# preamp.net
KiCad netlist of a schematic drawn in EAGLE
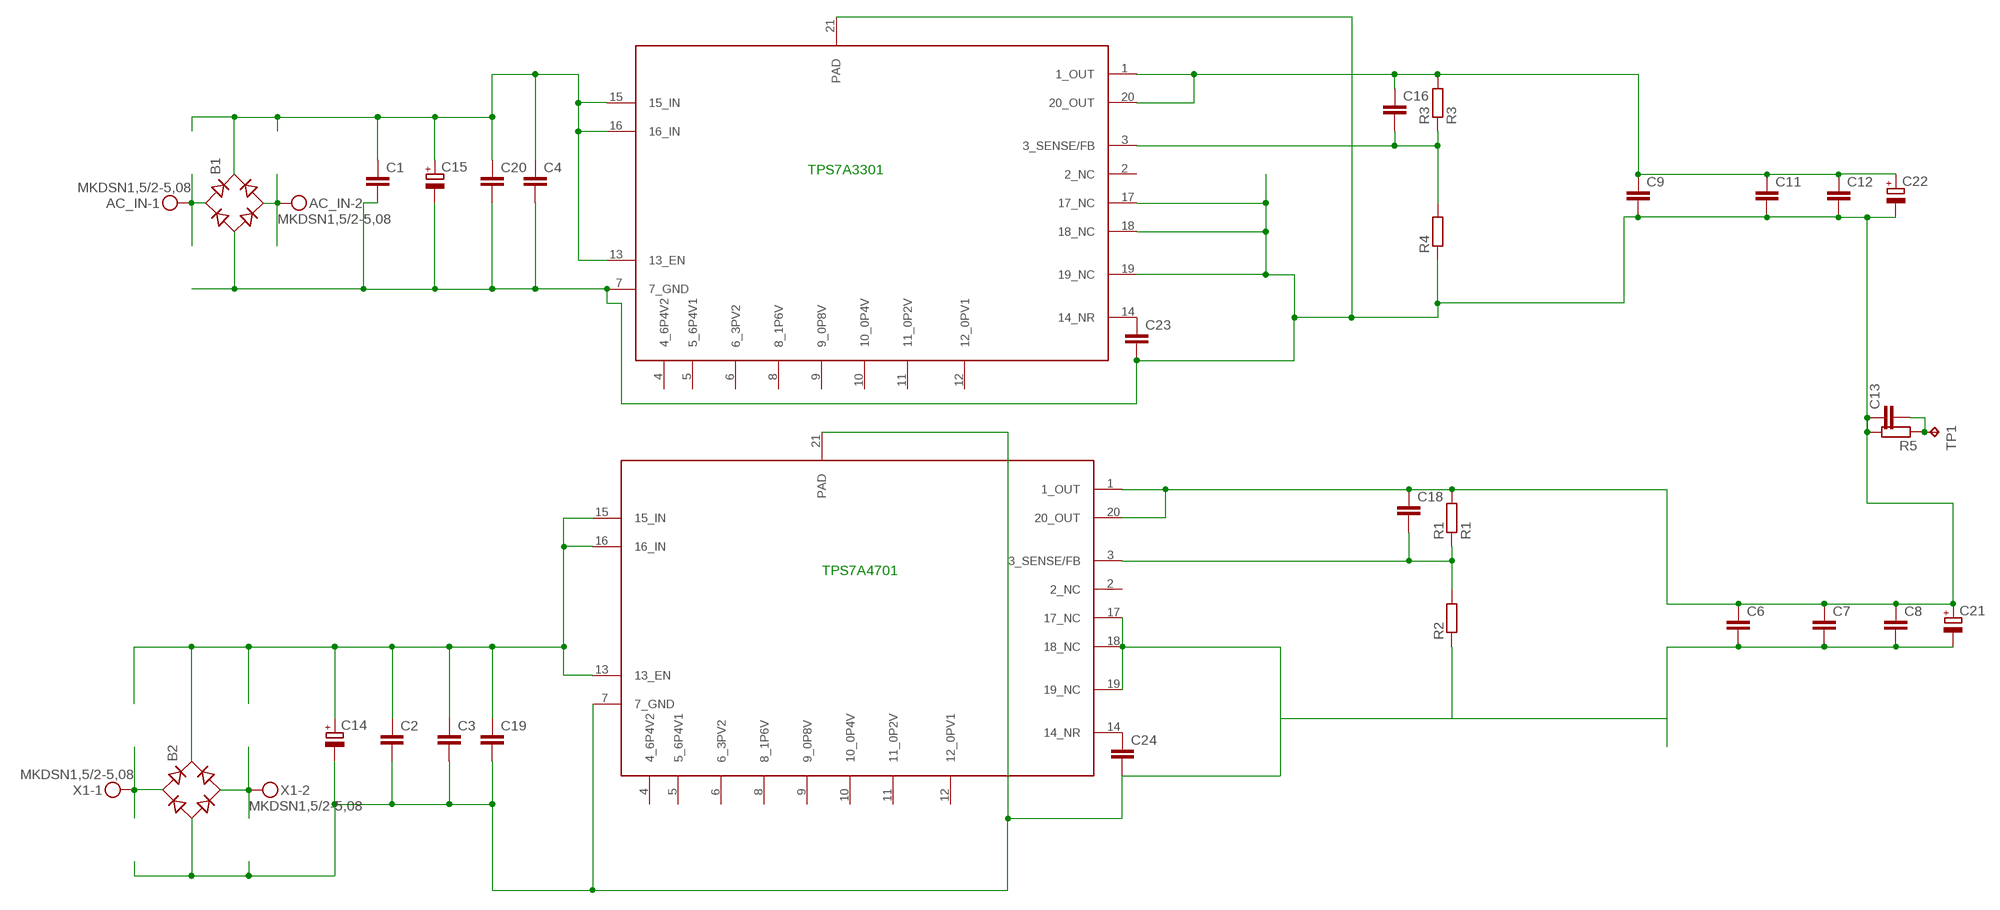
[diagram p0: schematic, sheet 1]
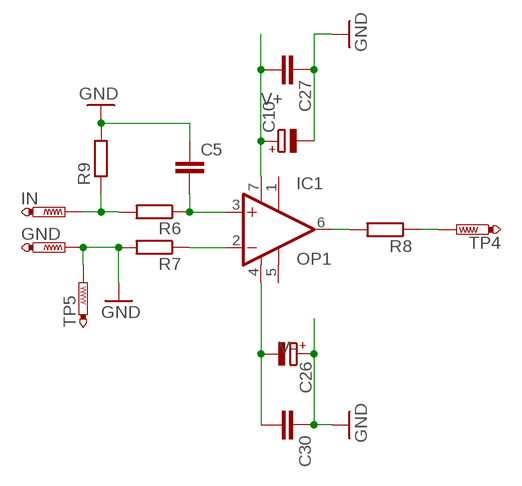
[diagram p1: schematic, sheet 2]

(export (version "E")
  (design (tool "Eeschema 10.0.6"))
  (components
    (comp (ref "AC_IN")
      (value "MKDSN1,5/2-5,08")
      (footprint "eagle-import:MKDSN1,5_2-5,08")
      (libsource (lib "eagle-import") (part "MKDSN1,5/2-5,08"))
    )
    (comp (ref "B1")
      (value "RB1A")
      (footprint "eagle-import:RB1A")
      (libsource (lib "eagle-import") (part "RB1A"))
    )
    (comp (ref "B2")
      (value "RB1A")
      (footprint "eagle-import:RB1A")
      (libsource (lib "eagle-import") (part "RB1A"))
    )
    (comp (ref "C1")
      (value "C-EUC1210")
      (footprint "eagle-import:C1210")
      (libsource (lib "eagle-import") (part "C-EUC1210"))
    )
    (comp (ref "C2")
      (value "C-EUC1210")
      (footprint "eagle-import:C1210")
      (libsource (lib "eagle-import") (part "C-EUC1210"))
    )
    (comp (ref "C3")
      (value "C-EUC0805")
      (footprint "eagle-import:C0805")
      (libsource (lib "eagle-import") (part "C-EUC0805"))
    )
    (comp (ref "C4")
      (value "C-EUC0805")
      (footprint "eagle-import:C0805")
      (libsource (lib "eagle-import") (part "C-EUC0805"))
    )
    (comp (ref "C6")
      (value "C-EUC0603")
      (footprint "eagle-import:C0603")
      (libsource (lib "eagle-import") (part "C-EUC0603"))
    )
    (comp (ref "C7")
      (value "C-EUC0805")
      (footprint "eagle-import:C0805")
      (libsource (lib "eagle-import") (part "C-EUC0805"))
    )
    (comp (ref "C8")
      (value "C-EUC1210")
      (footprint "eagle-import:C1210")
      (libsource (lib "eagle-import") (part "C-EUC1210"))
    )
    (comp (ref "C9")
      (value "C-EUC0603")
      (footprint "eagle-import:C0603")
      (libsource (lib "eagle-import") (part "C-EUC0603"))
    )
    (comp (ref "C11")
      (value "C-EUC1210")
      (footprint "eagle-import:C1210")
      (libsource (lib "eagle-import") (part "C-EUC1210"))
    )
    (comp (ref "C12")
      (value "C-EUC0805")
      (footprint "eagle-import:C0805")
      (libsource (lib "eagle-import") (part "C-EUC0805"))
    )
    (comp (ref "C13")
      (value "C-EU075-042X103")
      (footprint "eagle-import:C075-042X103")
      (libsource (lib "eagle-import") (part "C-EU075-042X103"))
    )
    (comp (ref "C14")
      (value "CPOL-EUE5-13")
      (footprint "eagle-import:E5-13")
      (libsource (lib "eagle-import") (part "CPOL-EUE5-13"))
    )
    (comp (ref "C15")
      (value "CPOL-EUE5-13")
      (footprint "eagle-import:E5-13")
      (libsource (lib "eagle-import") (part "CPOL-EUE5-13"))
    )
    (comp (ref "C16")
      (value "C-EUC0603")
      (footprint "eagle-import:C0603")
      (libsource (lib "eagle-import") (part "C-EUC0603"))
    )
    (comp (ref "C18")
      (value "C-EUC0603")
      (footprint "eagle-import:C0603")
      (libsource (lib "eagle-import") (part "C-EUC0603"))
    )
    (comp (ref "C19")
      (value "C-EUC0603")
      (footprint "eagle-import:C0603")
      (libsource (lib "eagle-import") (part "C-EUC0603"))
    )
    (comp (ref "C20")
      (value "C-EUC0603")
      (footprint "eagle-import:C0603")
      (libsource (lib "eagle-import") (part "C-EUC0603"))
    )
    (comp (ref "C21")
      (value "CPOL-EUE3.5-8")
      (footprint "eagle-import:E3,5-8")
      (libsource (lib "eagle-import") (part "CPOL-EUE3.5-8"))
    )
    (comp (ref "C22")
      (value "CPOL-EUE3.5-8")
      (footprint "eagle-import:E3,5-8")
      (libsource (lib "eagle-import") (part "CPOL-EUE3.5-8"))
    )
    (comp (ref "C23")
      (value "C-EUC0603")
      (footprint "eagle-import:C0603")
      (libsource (lib "eagle-import") (part "C-EUC0603"))
    )
    (comp (ref "C24")
      (value "C-EUC0603")
      (footprint "eagle-import:C0603")
      (libsource (lib "eagle-import") (part "C-EUC0603"))
    )
    (comp (ref "R1")
      (value "R1")
      (footprint "eagle-import:R0805")
      (libsource (lib "eagle-import") (part "R-EU_R0805"))
    )
    (comp (ref "R2")
      (value "R-EU_R0805")
      (footprint "eagle-import:R0805")
      (libsource (lib "eagle-import") (part "R-EU_R0805"))
    )
    (comp (ref "R3")
      (value "R3")
      (footprint "eagle-import:R0805")
      (libsource (lib "eagle-import") (part "R-EU_R0805"))
    )
    (comp (ref "R4")
      (value "R-EU_R0805")
      (footprint "eagle-import:R0805")
      (libsource (lib "eagle-import") (part "R-EU_R0805"))
    )
    (comp (ref "R5")
      (value "R-EU_0207/12")
      (footprint "eagle-import:0207_12")
      (libsource (lib "eagle-import") (part "R-EU_0207/12"))
    )
    (comp (ref "TP1")
      (value "TPPAD1-13")
      (footprint "eagle-import:P1-13")
      (libsource (lib "eagle-import") (part "TPPAD1-13"))
    )
    (comp (ref "U$1")
      (value "TPS7A4701")
      (footprint "eagle-import:QFN65P500X500X100-21N")
      (libsource (lib "eagle-import") (part "TPS7A4701"))
    )
    (comp (ref "U$2")
      (value "TPS7A4701")
      (footprint "eagle-import:QFN65P500X500X100-21N")
      (libsource (lib "eagle-import") (part "TPS7A4701"))
    )
    (comp (ref "X1")
      (value "MKDSN1,5/2-5,08")
      (footprint "eagle-import:MKDSN1,5_2-5,08")
      (libsource (lib "eagle-import") (part "MKDSN1,5/2-5,08"))
    )
    (comp (ref "C5")
      (value "C-EU050-045X075")
      (footprint "eagle-import:C050-045X075")
      (libsource (lib "eagle-import") (part "C-EU050-045X075"))
    )
    (comp (ref "C10")
      (value "CPOL-EUE5-8.5")
      (footprint "eagle-import:E5-8,5")
      (libsource (lib "eagle-import") (part "CPOL-EUE5-8.5"))
    )
    (comp (ref "C26")
      (value "CPOL-EUE5-8.5")
      (footprint "eagle-import:E5-8,5")
      (libsource (lib "eagle-import") (part "CPOL-EUE5-8.5"))
    )
    (comp (ref "C27")
      (value "C-EU050-030X075")
      (footprint "eagle-import:C050-030X075")
      (libsource (lib "eagle-import") (part "C-EU050-030X075"))
    )
    (comp (ref "C30")
      (value "C-EU050-030X075")
      (footprint "eagle-import:C050-030X075")
      (libsource (lib "eagle-import") (part "C-EU050-030X075"))
    )
    (comp (ref "GND")
      (value "PTR1PAD1-20")
      (footprint "eagle-import:P1-20")
      (libsource (lib "eagle-import") (part "PTR1PAD1-20"))
    )
    (comp (ref "IC1")
      (value "OP1")
      (footprint "eagle-import:DIL08")
      (fields (field (name "MF") "TEXAS INSTRUMENTS") (field (name "MPN") "OPA627BP"))
      (libsource (lib "eagle-import") (part "OPA627P"))
    )
    (comp (ref "IN")
      (value "PTR1PAD1-20")
      (footprint "eagle-import:P1-20")
      (libsource (lib "eagle-import") (part "PTR1PAD1-20"))
    )
    (comp (ref "R6")
      (value "R-EU_0207/10")
      (footprint "eagle-import:0207_10")
      (libsource (lib "eagle-import") (part "R-EU_0207/10"))
    )
    (comp (ref "R7")
      (value "R-EU_0207/10")
      (footprint "eagle-import:0207_10")
      (libsource (lib "eagle-import") (part "R-EU_0207/10"))
    )
    (comp (ref "R8")
      (value "R-EU_0207/10")
      (footprint "eagle-import:0207_10")
      (libsource (lib "eagle-import") (part "R-EU_0207/10"))
    )
    (comp (ref "R9")
      (value "R-EU_0207/10")
      (footprint "eagle-import:0207_10")
      (libsource (lib "eagle-import") (part "R-EU_0207/10"))
    )
    (comp (ref "TP4")
      (value "PTR1PAD1-20")
      (footprint "eagle-import:P1-20")
      (libsource (lib "eagle-import") (part "PTR1PAD1-20"))
    )
    (comp (ref "TP5")
      (value "PTR1PAD1-20")
      (footprint "eagle-import:P1-20")
      (libsource (lib "eagle-import") (part "PTR1PAD1-20"))
    )
  )
  (nets
    (net (code "1") (name "GND") (class "Default")
      (node (ref "B1") (pin "-") (pinfunction "-_-") (pintype "passive"))
      (node (ref "C1") (pin "2") (pinfunction "2_2") (pintype "passive"))
      (node (ref "C10") (pin "-") (pinfunction "-_-") (pintype "passive"))
      (node (ref "C11") (pin "2") (pinfunction "2_2") (pintype "passive"))
      (node (ref "C12") (pin "2") (pinfunction "2_2") (pintype "passive"))
      (node (ref "C13") (pin "1") (pinfunction "1_1") (pintype "passive"))
      (node (ref "C15") (pin "-") (pinfunction "-_-") (pintype "passive"))
      (node (ref "C18") (pin "1") (pinfunction "1_1") (pintype "passive"))
      (node (ref "C20") (pin "2") (pinfunction "2_2") (pintype "passive"))
      (node (ref "C21") (pin "+") (pinfunction "+_+") (pintype "passive"))
      (node (ref "C22") (pin "-") (pinfunction "-_-") (pintype "passive"))
      (node (ref "C23") (pin "2") (pinfunction "2_2") (pintype "passive"))
      (node (ref "C26") (pin "+") (pinfunction "+_+") (pintype "passive"))
      (node (ref "C27") (pin "1") (pinfunction "1_1") (pintype "passive"))
      (node (ref "C30") (pin "1") (pinfunction "1_1") (pintype "passive"))
      (node (ref "C4") (pin "2") (pinfunction "2_2") (pintype "passive"))
      (node (ref "C5") (pin "1") (pinfunction "1_1") (pintype "passive"))
      (node (ref "C6") (pin "1") (pinfunction "1_1") (pintype "passive"))
      (node (ref "C7") (pin "1") (pinfunction "1_1") (pintype "passive"))
      (node (ref "C8") (pin "1") (pinfunction "1_1") (pintype "passive"))
      (node (ref "C9") (pin "2") (pinfunction "2_2") (pintype "passive"))
      (node (ref "GND") (pin "TP") (pinfunction "TP_TP") (pintype "input"))
      (node (ref "R1") (pin "2") (pinfunction "2_2") (pintype "passive"))
      (node (ref "R4") (pin "1") (pinfunction "1_1") (pintype "passive"))
      (node (ref "R5") (pin "2") (pinfunction "2_2") (pintype "passive"))
      (node (ref "R7") (pin "2") (pinfunction "2_2") (pintype "passive"))
      (node (ref "R9") (pin "2") (pinfunction "2_2") (pintype "passive"))
      (node (ref "TP5") (pin "TP") (pinfunction "TP_TP") (pintype "input"))
      (node (ref "U$1") (pin "1") (pinfunction "1_OUT_1") (pintype "bidirectional"))
      (node (ref "U$1") (pin "20") (pinfunction "20_OUT_20") (pintype "bidirectional"))
      (node (ref "U$2") (pin "17") (pinfunction "17_NC_17") (pintype "bidirectional"))
      (node (ref "U$2") (pin "18") (pinfunction "18_NC_18") (pintype "bidirectional"))
      (node (ref "U$2") (pin "19") (pinfunction "19_NC_19") (pintype "bidirectional"))
      (node (ref "U$2") (pin "21") (pinfunction "PAD_21") (pintype "bidirectional"))
      (node (ref "U$2") (pin "7") (pinfunction "7_GND_7") (pintype "bidirectional"))
    )
    (net (code "2") (name "Net-(AC_INA-KL)") (class "Default")
      (node (ref "AC_IN") (pin "1") (pinfunction "KL_1") (pintype "passive"))
      (node (ref "B1") (pin "AC1") (pinfunction "AC1_AC1") (pintype "passive"))
    )
    (net (code "3") (name "Net-(AC_INB-KL)") (class "Default")
      (node (ref "AC_IN") (pin "2") (pinfunction "KL_2") (pintype "passive"))
      (node (ref "B1") (pin "AC2") (pinfunction "AC2_AC2") (pintype "passive"))
    )
    (net (code "4") (name "Net-(C13-Pad2)") (class "Default")
      (node (ref "C13") (pin "2") (pinfunction "2_2") (pintype "passive"))
      (node (ref "R5") (pin "1") (pinfunction "1_1") (pintype "passive"))
      (node (ref "TP1") (pin "TP") (pinfunction "TP_TP") (pintype "input"))
    )
    (net (code "5") (name "Net-(IC1-+IN)") (class "Default")
      (node (ref "C5") (pin "2") (pinfunction "2_2") (pintype "passive"))
      (node (ref "IC1") (pin "3") (pinfunction "+IN_3") (pintype "input"))
      (node (ref "R6") (pin "1") (pinfunction "1_1") (pintype "passive"))
    )
    (net (code "6") (name "Net-(IC1--IN)") (class "Default")
      (node (ref "IC1") (pin "2") (pinfunction "-IN_2") (pintype "input"))
      (node (ref "R7") (pin "1") (pinfunction "1_1") (pintype "passive"))
    )
    (net (code "7") (name "Net-(IC1-OUT)") (class "Default")
      (node (ref "IC1") (pin "6") (pinfunction "OUT_6") (pintype "output"))
      (node (ref "R8") (pin "2") (pinfunction "2_2") (pintype "passive"))
    )
    (net (code "8") (name "Net-(IN-PadTP)") (class "Default")
      (node (ref "IN") (pin "TP") (pinfunction "TP_TP") (pintype "input"))
      (node (ref "R6") (pin "2") (pinfunction "2_2") (pintype "passive"))
      (node (ref "R9") (pin "1") (pinfunction "1_1") (pintype "passive"))
    )
    (net (code "9") (name "Net-(R8-Pad1)") (class "Default")
      (node (ref "R8") (pin "1") (pinfunction "1_1") (pintype "passive"))
      (node (ref "TP4") (pin "TP") (pinfunction "TP_TP") (pintype "input"))
    )
    (net (code "10") (name "Net-(U$1-3_SENSE{slash}FB)") (class "Default")
      (node (ref "C18") (pin "2") (pinfunction "2_2") (pintype "passive"))
      (node (ref "R1") (pin "1") (pinfunction "1_1") (pintype "passive"))
      (node (ref "R2") (pin "2") (pinfunction "2_2") (pintype "passive"))
      (node (ref "U$1") (pin "3") (pinfunction "3_SENSE/FB_3") (pintype "bidirectional"))
    )
    (net (code "11") (name "Net-(U$1-13_EN)") (class "Default")
      (node (ref "B2") (pin "+") (pinfunction "+_+") (pintype "passive"))
      (node (ref "C14") (pin "+") (pinfunction "+_+") (pintype "passive"))
      (node (ref "C19") (pin "1") (pinfunction "1_1") (pintype "passive"))
      (node (ref "C2") (pin "1") (pinfunction "1_1") (pintype "passive"))
      (node (ref "C3") (pin "1") (pinfunction "1_1") (pintype "passive"))
      (node (ref "U$1") (pin "13") (pinfunction "13_EN_13") (pintype "bidirectional"))
      (node (ref "U$1") (pin "15") (pinfunction "15_IN_15") (pintype "bidirectional"))
      (node (ref "U$1") (pin "16") (pinfunction "16_IN_16") (pintype "bidirectional"))
    )
    (net (code "12") (name "Net-(U$1-14_NR)") (class "Default")
      (node (ref "C24") (pin "1") (pinfunction "1_1") (pintype "passive"))
      (node (ref "U$1") (pin "14") (pinfunction "14_NR_14") (pintype "bidirectional"))
    )
    (net (code "13") (name "Net-(U$2-3_SENSE{slash}FB)") (class "Default")
      (node (ref "C16") (pin "2") (pinfunction "2_2") (pintype "passive"))
      (node (ref "R3") (pin "1") (pinfunction "1_1") (pintype "passive"))
      (node (ref "R4") (pin "2") (pinfunction "2_2") (pintype "passive"))
      (node (ref "U$2") (pin "3") (pinfunction "3_SENSE/FB_3") (pintype "bidirectional"))
    )
    (net (code "14") (name "Net-(U$2-13_EN)") (class "Default")
      (node (ref "B1") (pin "+") (pinfunction "+_+") (pintype "passive"))
      (node (ref "C1") (pin "1") (pinfunction "1_1") (pintype "passive"))
      (node (ref "C15") (pin "+") (pinfunction "+_+") (pintype "passive"))
      (node (ref "C20") (pin "1") (pinfunction "1_1") (pintype "passive"))
      (node (ref "C4") (pin "1") (pinfunction "1_1") (pintype "passive"))
      (node (ref "U$2") (pin "13") (pinfunction "13_EN_13") (pintype "bidirectional"))
      (node (ref "U$2") (pin "15") (pinfunction "15_IN_15") (pintype "bidirectional"))
      (node (ref "U$2") (pin "16") (pinfunction "16_IN_16") (pintype "bidirectional"))
    )
    (net (code "15") (name "Net-(U$2-14_NR)") (class "Default")
      (node (ref "C23") (pin "1") (pinfunction "1_1") (pintype "passive"))
      (node (ref "U$2") (pin "14") (pinfunction "14_NR_14") (pintype "bidirectional"))
    )
    (net (code "16") (name "Net-(X1A-KL)") (class "Default")
      (node (ref "B2") (pin "AC1") (pinfunction "AC1_AC1") (pintype "passive"))
      (node (ref "X1") (pin "1") (pinfunction "KL_1") (pintype "passive"))
    )
    (net (code "17") (name "Net-(X1B-KL)") (class "Default")
      (node (ref "B2") (pin "AC2") (pinfunction "AC2_AC2") (pintype "passive"))
      (node (ref "X1") (pin "2") (pinfunction "KL_2") (pintype "passive"))
    )
    (net (code "18") (name "V+") (class "Default")
      (node (ref "C10") (pin "+") (pinfunction "+_+") (pintype "passive"))
      (node (ref "C11") (pin "1") (pinfunction "1_1") (pintype "passive"))
      (node (ref "C12") (pin "1") (pinfunction "1_1") (pintype "passive"))
      (node (ref "C16") (pin "1") (pinfunction "1_1") (pintype "passive"))
      (node (ref "C22") (pin "+") (pinfunction "+_+") (pintype "passive"))
      (node (ref "C27") (pin "2") (pinfunction "2_2") (pintype "passive"))
      (node (ref "C9") (pin "1") (pinfunction "1_1") (pintype "passive"))
      (node (ref "IC1") (pin "7") (pinfunction "V+_7") (pintype "power_in"))
      (node (ref "R3") (pin "2") (pinfunction "2_2") (pintype "passive"))
      (node (ref "U$2") (pin "1") (pinfunction "1_OUT_1") (pintype "bidirectional"))
      (node (ref "U$2") (pin "20") (pinfunction "20_OUT_20") (pintype "bidirectional"))
    )
    (net (code "19") (name "V-") (class "Default")
      (node (ref "B2") (pin "-") (pinfunction "-_-") (pintype "passive"))
      (node (ref "C14") (pin "-") (pinfunction "-_-") (pintype "passive"))
      (node (ref "C19") (pin "2") (pinfunction "2_2") (pintype "passive"))
      (node (ref "C2") (pin "2") (pinfunction "2_2") (pintype "passive"))
      (node (ref "C21") (pin "-") (pinfunction "-_-") (pintype "passive"))
      (node (ref "C24") (pin "2") (pinfunction "2_2") (pintype "passive"))
      (node (ref "C26") (pin "-") (pinfunction "-_-") (pintype "passive"))
      (node (ref "C3") (pin "2") (pinfunction "2_2") (pintype "passive"))
      (node (ref "C30") (pin "2") (pinfunction "2_2") (pintype "passive"))
      (node (ref "C6") (pin "2") (pinfunction "2_2") (pintype "passive"))
      (node (ref "C7") (pin "2") (pinfunction "2_2") (pintype "passive"))
      (node (ref "C8") (pin "2") (pinfunction "2_2") (pintype "passive"))
      (node (ref "IC1") (pin "4") (pinfunction "V-_4") (pintype "power_in"))
      (node (ref "R2") (pin "1") (pinfunction "1_1") (pintype "passive"))
      (node (ref "U$1") (pin "17") (pinfunction "17_NC_17") (pintype "bidirectional"))
      (node (ref "U$1") (pin "18") (pinfunction "18_NC_18") (pintype "bidirectional"))
      (node (ref "U$1") (pin "19") (pinfunction "19_NC_19") (pintype "bidirectional"))
      (node (ref "U$1") (pin "21") (pinfunction "PAD_21") (pintype "bidirectional"))
      (node (ref "U$1") (pin "7") (pinfunction "7_GND_7") (pintype "bidirectional"))
    )
    (net (code "20") (name "unconnected-(IC1-TRIM1-Pad1)") (class "Default")
      (node (ref "IC1") (pin "1") (pinfunction "TRIM1_1") (pintype "passive"))
    )
    (net (code "21") (name "unconnected-(IC1-TRIM2-Pad5)") (class "Default")
      (node (ref "IC1") (pin "5") (pinfunction "TRIM2_5") (pintype "passive"))
    )
    (net (code "22") (name "unconnected-(U$1-2_NC-Pad2)") (class "Default")
      (node (ref "U$1") (pin "2") (pinfunction "2_NC_2") (pintype "bidirectional"))
    )
    (net (code "23") (name "unconnected-(U$1-4_6P4V2-Pad4)") (class "Default")
      (node (ref "U$1") (pin "4") (pinfunction "4_6P4V2_4") (pintype "bidirectional"))
    )
    (net (code "24") (name "unconnected-(U$1-5_6P4V1-Pad5)") (class "Default")
      (node (ref "U$1") (pin "5") (pinfunction "5_6P4V1_5") (pintype "bidirectional"))
    )
    (net (code "25") (name "unconnected-(U$1-6_3PV2-Pad6)") (class "Default")
      (node (ref "U$1") (pin "6") (pinfunction "6_3PV2_6") (pintype "bidirectional"))
    )
    (net (code "26") (name "unconnected-(U$1-8_1P6V-Pad8)") (class "Default")
      (node (ref "U$1") (pin "8") (pinfunction "8_1P6V_8") (pintype "bidirectional"))
    )
    (net (code "27") (name "unconnected-(U$1-9_0P8V-Pad9)") (class "Default")
      (node (ref "U$1") (pin "9") (pinfunction "9_0P8V_9") (pintype "bidirectional"))
    )
    (net (code "28") (name "unconnected-(U$1-10_0P4V-Pad10)") (class "Default")
      (node (ref "U$1") (pin "10") (pinfunction "10_0P4V_10") (pintype "bidirectional"))
    )
    (net (code "29") (name "unconnected-(U$1-11_0P2V-Pad11)") (class "Default")
      (node (ref "U$1") (pin "11") (pinfunction "11_0P2V_11") (pintype "bidirectional"))
    )
    (net (code "30") (name "unconnected-(U$1-12_0PV1-Pad12)") (class "Default")
      (node (ref "U$1") (pin "12") (pinfunction "12_0PV1_12") (pintype "bidirectional"))
    )
    (net (code "31") (name "unconnected-(U$2-2_NC-Pad2)") (class "Default")
      (node (ref "U$2") (pin "2") (pinfunction "2_NC_2") (pintype "bidirectional"))
    )
    (net (code "32") (name "unconnected-(U$2-4_6P4V2-Pad4)") (class "Default")
      (node (ref "U$2") (pin "4") (pinfunction "4_6P4V2_4") (pintype "bidirectional"))
    )
    (net (code "33") (name "unconnected-(U$2-5_6P4V1-Pad5)") (class "Default")
      (node (ref "U$2") (pin "5") (pinfunction "5_6P4V1_5") (pintype "bidirectional"))
    )
    (net (code "34") (name "unconnected-(U$2-6_3PV2-Pad6)") (class "Default")
      (node (ref "U$2") (pin "6") (pinfunction "6_3PV2_6") (pintype "bidirectional"))
    )
    (net (code "35") (name "unconnected-(U$2-8_1P6V-Pad8)") (class "Default")
      (node (ref "U$2") (pin "8") (pinfunction "8_1P6V_8") (pintype "bidirectional"))
    )
    (net (code "36") (name "unconnected-(U$2-9_0P8V-Pad9)") (class "Default")
      (node (ref "U$2") (pin "9") (pinfunction "9_0P8V_9") (pintype "bidirectional"))
    )
    (net (code "37") (name "unconnected-(U$2-10_0P4V-Pad10)") (class "Default")
      (node (ref "U$2") (pin "10") (pinfunction "10_0P4V_10") (pintype "bidirectional"))
    )
    (net (code "38") (name "unconnected-(U$2-11_0P2V-Pad11)") (class "Default")
      (node (ref "U$2") (pin "11") (pinfunction "11_0P2V_11") (pintype "bidirectional"))
    )
    (net (code "39") (name "unconnected-(U$2-12_0PV1-Pad12)") (class "Default")
      (node (ref "U$2") (pin "12") (pinfunction "12_0PV1_12") (pintype "bidirectional"))
    )
  )
)
